# Suits_Board.net
KiCad netlist of a schematic drawn in EAGLE
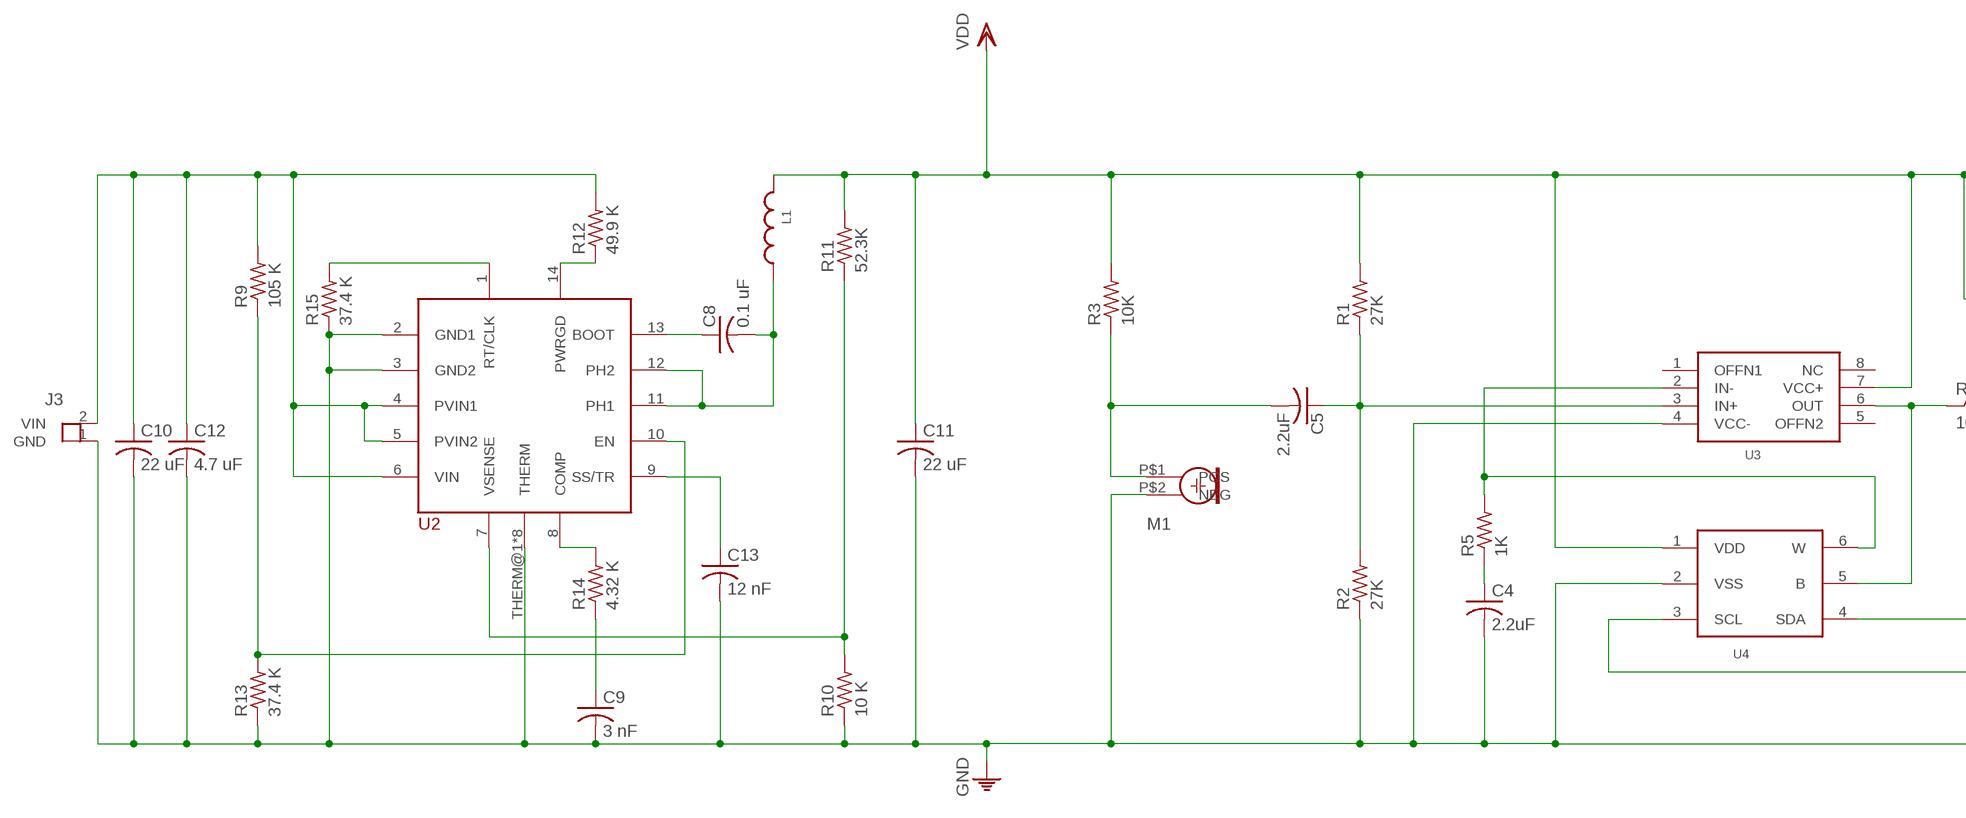
[diagram p0: schematic, sheet 1, part 1 of 2]
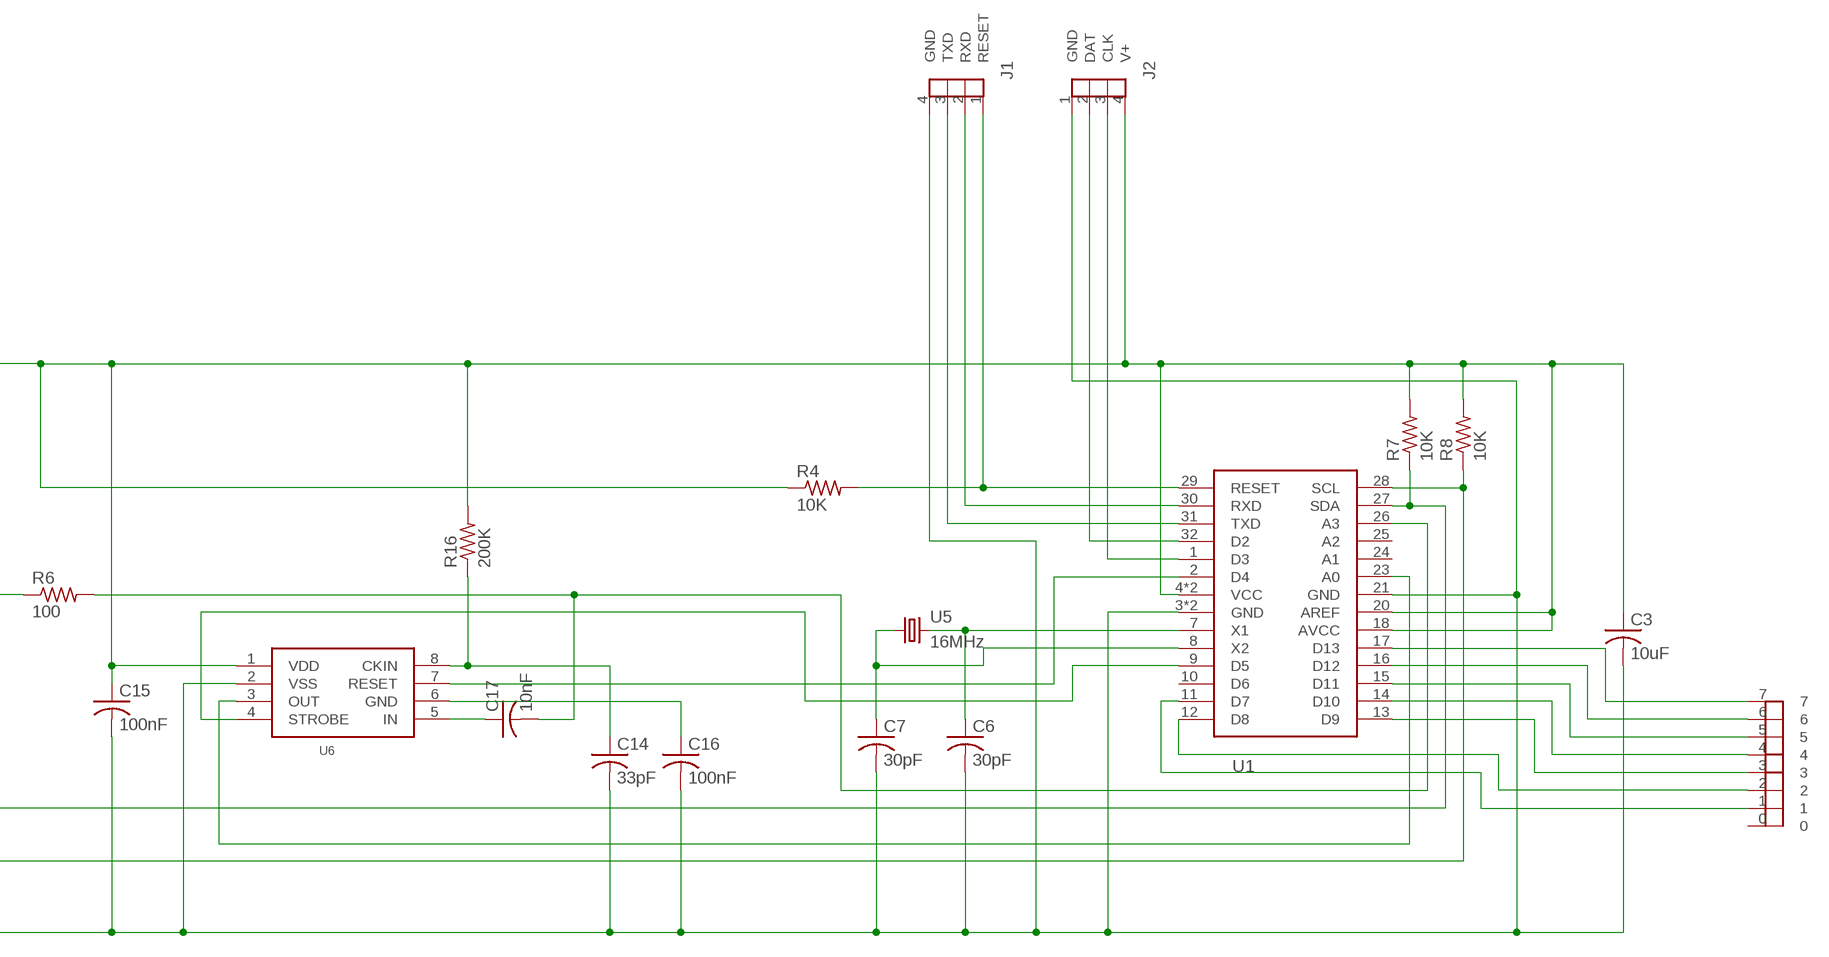
[diagram p1: schematic, sheet 1, part 2 of 2]

(export (version "E")
  (design (tool "Eeschema 10.0.6"))
  (components
    (comp (ref "C3")
      (value "10uF")
      (footprint "eagle-import:0805")
      (libsource (lib "eagle-import") (part "CAP0805"))
    )
    (comp (ref "C4")
      (value "2.2uF")
      (footprint "eagle-import:0603")
      (libsource (lib "eagle-import") (part "CAP0603"))
    )
    (comp (ref "C5")
      (value "2.2uF")
      (footprint "eagle-import:0603")
      (libsource (lib "eagle-import") (part "CAP0603"))
    )
    (comp (ref "C6")
      (value "30pF")
      (footprint "eagle-import:0603")
      (libsource (lib "eagle-import") (part "CAP0603"))
    )
    (comp (ref "C7")
      (value "30pF")
      (footprint "eagle-import:0603")
      (libsource (lib "eagle-import") (part "CAP0603"))
    )
    (comp (ref "C8")
      (value "0.1 uF")
      (footprint "eagle-import:0805")
      (libsource (lib "eagle-import") (part "CAP0805"))
    )
    (comp (ref "C9")
      (value "3 nF")
      (footprint "eagle-import:0805")
      (libsource (lib "eagle-import") (part "CAP0805"))
    )
    (comp (ref "C10")
      (value "22 uF")
      (footprint "eagle-import:1210")
      (libsource (lib "eagle-import") (part "CAP1210"))
    )
    (comp (ref "C11")
      (value "22 uF")
      (footprint "eagle-import:1210")
      (libsource (lib "eagle-import") (part "CAP1210"))
    )
    (comp (ref "C12")
      (value "4.7 uF")
      (footprint "eagle-import:0805")
      (libsource (lib "eagle-import") (part "CAP0805"))
    )
    (comp (ref "C13")
      (value "12 nF")
      (footprint "eagle-import:0402")
      (libsource (lib "eagle-import") (part "CAP0402"))
    )
    (comp (ref "C14")
      (value "33pF")
      (footprint "eagle-import:0402")
      (libsource (lib "eagle-import") (part "CAP0402"))
    )
    (comp (ref "C15")
      (value "100nF")
      (footprint "eagle-import:0805")
      (libsource (lib "eagle-import") (part "CAP0805"))
    )
    (comp (ref "C16")
      (value "100nF")
      (footprint "eagle-import:0805")
      (libsource (lib "eagle-import") (part "CAP0805"))
    )
    (comp (ref "C17")
      (value "10nF")
      (footprint "eagle-import:0402")
      (libsource (lib "eagle-import") (part "CAP0402"))
    )
    (comp (ref "J1")
      (value "PRGMCONN")
      (footprint "eagle-import:4CONN")
      (libsource (lib "eagle-import") (part "PRGMCONN"))
    )
    (comp (ref "J2")
      (value "LEDCONN")
      (footprint "eagle-import:4CONN")
      (libsource (lib "eagle-import") (part "LEDCONN"))
    )
    (comp (ref "J3")
      (value "PWRCONN")
      (footprint "eagle-import:2CONN")
      (libsource (lib "eagle-import") (part "PWRCONN"))
    )
    (comp (ref "L1")
      (value "VLF10045T")
      (footprint "eagle-import:VLF10045")
      (libsource (lib "eagle-import") (part "VLF10045T"))
    )
    (comp (ref "M1")
      (value "ELEC_MIC")
      (footprint "eagle-import:ELEC_MIC")
      (libsource (lib "eagle-import") (part "ELEC_MIC"))
    )
    (comp (ref "R1")
      (value "27K")
      (footprint "eagle-import:0603")
      (libsource (lib "eagle-import") (part "RESISTOR"))
    )
    (comp (ref "R2")
      (value "27K")
      (footprint "eagle-import:0603")
      (libsource (lib "eagle-import") (part "RESISTOR"))
    )
    (comp (ref "R3")
      (value "10K")
      (footprint "eagle-import:0603")
      (libsource (lib "eagle-import") (part "RESISTOR"))
    )
    (comp (ref "R4")
      (value "10K")
      (footprint "eagle-import:0603")
      (libsource (lib "eagle-import") (part "RESISTOR"))
    )
    (comp (ref "R5")
      (value "1K")
      (footprint "eagle-import:0603")
      (libsource (lib "eagle-import") (part "RESISTOR"))
    )
    (comp (ref "R6")
      (value "100")
      (footprint "eagle-import:0603")
      (libsource (lib "eagle-import") (part "RESISTOR"))
    )
    (comp (ref "R7")
      (value "10K")
      (footprint "eagle-import:0603")
      (libsource (lib "eagle-import") (part "RESISTOR"))
    )
    (comp (ref "R8")
      (value "10K")
      (footprint "eagle-import:0603")
      (libsource (lib "eagle-import") (part "RESISTOR"))
    )
    (comp (ref "R9")
      (value "105 K")
      (footprint "eagle-import:0402")
      (libsource (lib "eagle-import") (part "R0402"))
    )
    (comp (ref "R10")
      (value "10 K")
      (footprint "eagle-import:0402")
      (libsource (lib "eagle-import") (part "R0402"))
    )
    (comp (ref "R11")
      (value "52.3K")
      (footprint "eagle-import:0402")
      (libsource (lib "eagle-import") (part "R0402"))
    )
    (comp (ref "R12")
      (value "49.9 K")
      (footprint "eagle-import:0402")
      (libsource (lib "eagle-import") (part "R0402"))
    )
    (comp (ref "R13")
      (value "37.4 K")
      (footprint "eagle-import:0402")
      (libsource (lib "eagle-import") (part "R0402"))
    )
    (comp (ref "R14")
      (value "4.32 K")
      (footprint "eagle-import:0402")
      (libsource (lib "eagle-import") (part "R0402"))
    )
    (comp (ref "R15")
      (value "37.4 K")
      (footprint "eagle-import:0402")
      (libsource (lib "eagle-import") (part "R0402"))
    )
    (comp (ref "R16")
      (value "200K")
      (footprint "eagle-import:0603")
      (libsource (lib "eagle-import") (part "RESISTOR"))
    )
    (comp (ref "U$1")
      (value "KEYPAD")
      (footprint "eagle-import:KEYPAD")
      (libsource (lib "eagle-import") (part "KEYPAD"))
    )
    (comp (ref "U1")
      (value "ATMEGA328P")
      (footprint "eagle-import:TQFP32-08")
      (libsource (lib "eagle-import") (part "ATMEGA328P"))
    )
    (comp (ref "U2")
      (value "TPS54620")
      (footprint "eagle-import:14-VFQFN")
      (libsource (lib "eagle-import") (part "TPS54620"))
    )
    (comp (ref "U3")
      (value "TL071")
      (footprint "eagle-import:8-SOIC")
      (libsource (lib "eagle-import") (part "TL071"))
    )
    (comp (ref "U4")
      (value "MCP4017")
      (footprint "eagle-import:SOT-363")
      (libsource (lib "eagle-import") (part "MCP4017"))
    )
    (comp (ref "U5")
      (value "16MHz")
      (footprint "eagle-import:HC49_US")
      (libsource (lib "eagle-import") (part "CRYSTAL"))
    )
    (comp (ref "U6")
      (value "FFT IC")
      (footprint "eagle-import:DIP8")
      (libsource (lib "eagle-import") (part "MSGEQ7"))
    )
  )
  (nets
    (net (code "1") (name "GND") (class "Default")
      (node (ref "C10") (pin "P$2") (pinfunction "2_P$2") (pintype "passive"))
      (node (ref "C11") (pin "P$2") (pinfunction "2_P$2") (pintype "passive"))
      (node (ref "C12") (pin "A1") (pinfunction "2_A1") (pintype "passive"))
      (node (ref "C13") (pin "P$2") (pinfunction "2_P$2") (pintype "passive"))
      (node (ref "C14") (pin "P$2") (pinfunction "2_P$2") (pintype "passive"))
      (node (ref "C15") (pin "A1") (pinfunction "2_A1") (pintype "passive"))
      (node (ref "C16") (pin "A1") (pinfunction "2_A1") (pintype "passive"))
      (node (ref "C3") (pin "A1") (pinfunction "2_A1") (pintype "passive"))
      (node (ref "C4") (pin "2") (pinfunction "2_2") (pintype "passive"))
      (node (ref "C6") (pin "2") (pinfunction "2_2") (pintype "passive"))
      (node (ref "C7") (pin "2") (pinfunction "2_2") (pintype "passive"))
      (node (ref "C9") (pin "A1") (pinfunction "2_A1") (pintype "passive"))
      (node (ref "J1") (pin "4") (pinfunction "GND_4") (pintype "bidirectional"))
      (node (ref "J2") (pin "1") (pinfunction "GND_1") (pintype "bidirectional"))
      (node (ref "J3") (pin "1") (pinfunction "GND_1") (pintype "bidirectional"))
      (node (ref "M1") (pin "P$2") (pinfunction "NEG_P$2") (pintype "passive"))
      (node (ref "R10") (pin "P$1") (pinfunction "1_P$1") (pintype "passive"))
      (node (ref "R13") (pin "P$1") (pinfunction "1_P$1") (pintype "passive"))
      (node (ref "R15") (pin "P$1") (pinfunction "1_P$1") (pintype "passive"))
      (node (ref "R2") (pin "1") (pinfunction "1_1") (pintype "passive"))
      (node (ref "U1") (pin "21") (pinfunction "GND_21") (pintype "bidirectional"))
      (node (ref "U1") (pin "3") (pinfunction "GND_3") (pintype "bidirectional"))
      (node (ref "U1") (pin "5") (pinfunction "GND_5") (pintype "bidirectional"))
      (node (ref "U2") (pin "2") (pinfunction "GND1_2") (pintype "bidirectional"))
      (node (ref "U2") (pin "3") (pinfunction "GND2_3") (pintype "bidirectional"))
      (node (ref "U2") (pin "THERM@1") (pinfunction "THERM_THERM@1") (pintype "bidirectional"))
      (node (ref "U2") (pin "THERM@2") (pinfunction "THERM_THERM@2") (pintype "bidirectional"))
      (node (ref "U2") (pin "THERM@3") (pinfunction "THERM_THERM@3") (pintype "bidirectional"))
      (node (ref "U2") (pin "THERM@4") (pinfunction "THERM_THERM@4") (pintype "bidirectional"))
      (node (ref "U2") (pin "THERM@5") (pinfunction "THERM_THERM@5") (pintype "bidirectional"))
      (node (ref "U2") (pin "THERM@6") (pinfunction "THERM_THERM@6") (pintype "bidirectional"))
      (node (ref "U2") (pin "THERM@7") (pinfunction "THERM_THERM@7") (pintype "bidirectional"))
      (node (ref "U2") (pin "THERM@8") (pinfunction "THERM_THERM@8") (pintype "bidirectional"))
      (node (ref "U3") (pin "4") (pinfunction "VCC-_4") (pintype "bidirectional"))
      (node (ref "U4") (pin "2") (pinfunction "VSS_2") (pintype "bidirectional"))
      (node (ref "U6") (pin "2") (pinfunction "VSS_2") (pintype "bidirectional"))
    )
    (net (code "2") (name "Net-(C4-Pad1)") (class "Default")
      (node (ref "C4") (pin "1") (pinfunction "1_1") (pintype "passive"))
      (node (ref "R5") (pin "1") (pinfunction "1_1") (pintype "passive"))
    )
    (net (code "3") (name "Net-(C8-1)") (class "Default")
      (node (ref "C8") (pin "A") (pinfunction "1_A") (pintype "passive"))
      (node (ref "U2") (pin "13") (pinfunction "BOOT_13") (pintype "bidirectional"))
    )
    (net (code "4") (name "Net-(C8-2)") (class "Default")
      (node (ref "C8") (pin "A1") (pinfunction "2_A1") (pintype "passive"))
      (node (ref "L1") (pin "P$1") (pinfunction "1_P$1") (pintype "passive"))
      (node (ref "U2") (pin "11") (pinfunction "PH1_11") (pintype "bidirectional"))
      (node (ref "U2") (pin "12") (pinfunction "PH2_12") (pintype "bidirectional"))
    )
    (net (code "5") (name "Net-(C9-1)") (class "Default")
      (node (ref "C9") (pin "A") (pinfunction "1_A") (pintype "passive"))
      (node (ref "R14") (pin "P$1") (pinfunction "1_P$1") (pintype "passive"))
    )
    (net (code "6") (name "Net-(C10-1)") (class "Default")
      (node (ref "C10") (pin "P$1") (pinfunction "1_P$1") (pintype "passive"))
      (node (ref "C12") (pin "A") (pinfunction "1_A") (pintype "passive"))
      (node (ref "J3") (pin "2") (pinfunction "VIN_2") (pintype "bidirectional"))
      (node (ref "R12") (pin "P$2") (pinfunction "2_P$2") (pintype "passive"))
      (node (ref "R9") (pin "P$2") (pinfunction "2_P$2") (pintype "passive"))
      (node (ref "U2") (pin "4") (pinfunction "PVIN1_4") (pintype "bidirectional"))
      (node (ref "U2") (pin "5") (pinfunction "PVIN2_5") (pintype "bidirectional"))
      (node (ref "U2") (pin "6") (pinfunction "VIN_6") (pintype "bidirectional"))
    )
    (net (code "7") (name "Net-(C13-1)") (class "Default")
      (node (ref "C13") (pin "P$1") (pinfunction "1_P$1") (pintype "passive"))
      (node (ref "U2") (pin "9") (pinfunction "SS/TR_9") (pintype "bidirectional"))
    )
    (net (code "8") (name "Net-(C14-1)") (class "Default")
      (node (ref "C14") (pin "P$1") (pinfunction "1_P$1") (pintype "passive"))
      (node (ref "R16") (pin "1") (pinfunction "1_1") (pintype "passive"))
      (node (ref "U6") (pin "8") (pinfunction "CKIN_8") (pintype "bidirectional"))
    )
    (net (code "9") (name "Net-(C16-1)") (class "Default")
      (node (ref "C16") (pin "A") (pinfunction "1_A") (pintype "passive"))
      (node (ref "U6") (pin "6") (pinfunction "GND_6") (pintype "bidirectional"))
    )
    (net (code "10") (name "Net-(C17-1)") (class "Default")
      (node (ref "C17") (pin "P$1") (pinfunction "1_P$1") (pintype "passive"))
      (node (ref "U6") (pin "5") (pinfunction "IN_5") (pintype "bidirectional"))
    )
    (net (code "11") (name "Net-(C17-2)") (class "Default")
      (node (ref "C17") (pin "P$2") (pinfunction "2_P$2") (pintype "passive"))
      (node (ref "R6") (pin "2") (pinfunction "2_2") (pintype "passive"))
      (node (ref "U1") (pin "26") (pinfunction "A3_26") (pintype "bidirectional"))
    )
    (net (code "12") (name "Net-(J1-RESET)") (class "Default")
      (node (ref "J1") (pin "1") (pinfunction "RESET_1") (pintype "bidirectional"))
      (node (ref "R4") (pin "2") (pinfunction "2_2") (pintype "passive"))
      (node (ref "U1") (pin "29") (pinfunction "RESET_29") (pintype "bidirectional"))
    )
    (net (code "13") (name "Net-(J1-RXD)") (class "Default")
      (node (ref "J1") (pin "2") (pinfunction "RXD_2") (pintype "bidirectional"))
      (node (ref "U1") (pin "30") (pinfunction "RXD_30") (pintype "bidirectional"))
    )
    (net (code "14") (name "Net-(J1-TXD)") (class "Default")
      (node (ref "J1") (pin "3") (pinfunction "TXD_3") (pintype "bidirectional"))
      (node (ref "U1") (pin "31") (pinfunction "TXD_31") (pintype "bidirectional"))
    )
    (net (code "15") (name "Net-(J2-CLK)") (class "Default")
      (node (ref "J2") (pin "3") (pinfunction "CLK_3") (pintype "bidirectional"))
      (node (ref "U1") (pin "1") (pinfunction "D3_1") (pintype "bidirectional"))
    )
    (net (code "16") (name "Net-(J2-DAT)") (class "Default")
      (node (ref "J2") (pin "2") (pinfunction "DAT_2") (pintype "bidirectional"))
      (node (ref "U1") (pin "32") (pinfunction "D2_32") (pintype "bidirectional"))
    )
    (net (code "17") (name "Net-(M1-POS)") (class "Default")
      (node (ref "C5") (pin "2") (pinfunction "2_2") (pintype "passive"))
      (node (ref "M1") (pin "P$1") (pinfunction "POS_P$1") (pintype "passive"))
      (node (ref "R3") (pin "1") (pinfunction "1_1") (pintype "passive"))
    )
    (net (code "18") (name "Net-(R10-2)") (class "Default")
      (node (ref "R10") (pin "P$2") (pinfunction "2_P$2") (pintype "passive"))
      (node (ref "R11") (pin "P$1") (pinfunction "1_P$1") (pintype "passive"))
      (node (ref "U2") (pin "7") (pinfunction "VSENSE_7") (pintype "bidirectional"))
    )
    (net (code "19") (name "Net-(R12-1)") (class "Default")
      (node (ref "R12") (pin "P$1") (pinfunction "1_P$1") (pintype "passive"))
      (node (ref "U2") (pin "14") (pinfunction "PWRGD_14") (pintype "bidirectional"))
    )
    (net (code "20") (name "Net-(R13-2)") (class "Default")
      (node (ref "R13") (pin "P$2") (pinfunction "2_P$2") (pintype "passive"))
      (node (ref "R9") (pin "P$1") (pinfunction "1_P$1") (pintype "passive"))
      (node (ref "U2") (pin "10") (pinfunction "EN_10") (pintype "bidirectional"))
    )
    (net (code "21") (name "Net-(R14-2)") (class "Default")
      (node (ref "R14") (pin "P$2") (pinfunction "2_P$2") (pintype "passive"))
      (node (ref "U2") (pin "8") (pinfunction "COMP_8") (pintype "bidirectional"))
    )
    (net (code "22") (name "Net-(R15-2)") (class "Default")
      (node (ref "R15") (pin "P$2") (pinfunction "2_P$2") (pintype "passive"))
      (node (ref "U2") (pin "1") (pinfunction "RT/CLK_1") (pintype "bidirectional"))
    )
    (net (code "23") (name "Net-(U1-A0)") (class "Default")
      (node (ref "U1") (pin "23") (pinfunction "A0_23") (pintype "bidirectional"))
      (node (ref "U6") (pin "3") (pinfunction "OUT_3") (pintype "bidirectional"))
    )
    (net (code "24") (name "Net-(U1-D4)") (class "Default")
      (node (ref "U1") (pin "2") (pinfunction "D4_2") (pintype "bidirectional"))
      (node (ref "U6") (pin "7") (pinfunction "RESET_7") (pintype "bidirectional"))
    )
    (net (code "25") (name "Net-(U1-D5)") (class "Default")
      (node (ref "U1") (pin "9") (pinfunction "D5_9") (pintype "bidirectional"))
      (node (ref "U6") (pin "4") (pinfunction "STROBE_4") (pintype "bidirectional"))
    )
    (net (code "26") (name "Net-(U1-D7)") (class "Default")
      (node (ref "U$1") (pin "1") (pinfunction "1_1") (pintype "bidirectional"))
      (node (ref "U1") (pin "11") (pinfunction "D7_11") (pintype "bidirectional"))
    )
    (net (code "27") (name "Net-(U1-D8)") (class "Default")
      (node (ref "U$1") (pin "2") (pinfunction "2_2") (pintype "bidirectional"))
      (node (ref "U1") (pin "12") (pinfunction "D8_12") (pintype "bidirectional"))
    )
    (net (code "28") (name "Net-(U1-D9)") (class "Default")
      (node (ref "U$1") (pin "3") (pinfunction "3_3") (pintype "bidirectional"))
      (node (ref "U1") (pin "13") (pinfunction "D9_13") (pintype "bidirectional"))
    )
    (net (code "29") (name "Net-(U1-D10)") (class "Default")
      (node (ref "U$1") (pin "4") (pinfunction "4_4") (pintype "bidirectional"))
      (node (ref "U1") (pin "14") (pinfunction "D10_14") (pintype "bidirectional"))
    )
    (net (code "30") (name "Net-(U1-D11)") (class "Default")
      (node (ref "U$1") (pin "5") (pinfunction "5_5") (pintype "bidirectional"))
      (node (ref "U1") (pin "15") (pinfunction "D11_15") (pintype "bidirectional"))
    )
    (net (code "31") (name "Net-(U1-D12)") (class "Default")
      (node (ref "U$1") (pin "6") (pinfunction "6_6") (pintype "bidirectional"))
      (node (ref "U1") (pin "16") (pinfunction "D12_16") (pintype "bidirectional"))
    )
    (net (code "32") (name "Net-(U1-D13)") (class "Default")
      (node (ref "U$1") (pin "7") (pinfunction "7_7") (pintype "bidirectional"))
      (node (ref "U1") (pin "17") (pinfunction "D13_17") (pintype "bidirectional"))
    )
    (net (code "33") (name "Net-(U1-SCL)") (class "Default")
      (node (ref "R8") (pin "1") (pinfunction "1_1") (pintype "passive"))
      (node (ref "U1") (pin "28") (pinfunction "SCL_28") (pintype "bidirectional"))
      (node (ref "U4") (pin "3") (pinfunction "SCL_3") (pintype "bidirectional"))
    )
    (net (code "34") (name "Net-(U1-SDA)") (class "Default")
      (node (ref "R7") (pin "1") (pinfunction "1_1") (pintype "passive"))
      (node (ref "U1") (pin "27") (pinfunction "SDA_27") (pintype "bidirectional"))
      (node (ref "U4") (pin "4") (pinfunction "SDA_4") (pintype "bidirectional"))
    )
    (net (code "35") (name "Net-(U1-X1)") (class "Default")
      (node (ref "C6") (pin "1") (pinfunction "1_1") (pintype "passive"))
      (node (ref "U1") (pin "7") (pinfunction "X1_7") (pintype "bidirectional"))
      (node (ref "U5") (pin "P$2") (pinfunction "2_P$2") (pintype "passive"))
    )
    (net (code "36") (name "Net-(U1-X2)") (class "Default")
      (node (ref "C7") (pin "1") (pinfunction "1_1") (pintype "passive"))
      (node (ref "U1") (pin "8") (pinfunction "X2_8") (pintype "bidirectional"))
      (node (ref "U5") (pin "P$1") (pinfunction "1_P$1") (pintype "passive"))
    )
    (net (code "37") (name "Net-(U3-IN+)") (class "Default")
      (node (ref "C5") (pin "1") (pinfunction "1_1") (pintype "passive"))
      (node (ref "R1") (pin "1") (pinfunction "1_1") (pintype "passive"))
      (node (ref "R2") (pin "2") (pinfunction "2_2") (pintype "passive"))
      (node (ref "U3") (pin "3") (pinfunction "IN+_3") (pintype "bidirectional"))
    )
    (net (code "38") (name "Net-(U3-IN-)") (class "Default")
      (node (ref "R5") (pin "2") (pinfunction "2_2") (pintype "passive"))
      (node (ref "U3") (pin "2") (pinfunction "IN-_2") (pintype "bidirectional"))
      (node (ref "U4") (pin "6") (pinfunction "W_6") (pintype "bidirectional"))
    )
    (net (code "39") (name "Net-(U3-OUT)") (class "Default")
      (node (ref "R6") (pin "1") (pinfunction "1_1") (pintype "passive"))
      (node (ref "U3") (pin "6") (pinfunction "OUT_6") (pintype "bidirectional"))
      (node (ref "U4") (pin "5") (pinfunction "B_5") (pintype "bidirectional"))
    )
    (net (code "40") (name "VDD") (class "Default")
      (node (ref "C11") (pin "P$1") (pinfunction "1_P$1") (pintype "passive"))
      (node (ref "C15") (pin "A") (pinfunction "1_A") (pintype "passive"))
      (node (ref "C3") (pin "A") (pinfunction "1_A") (pintype "passive"))
      (node (ref "J2") (pin "4") (pinfunction "V+_4") (pintype "bidirectional"))
      (node (ref "L1") (pin "P$2") (pinfunction "2_P$2") (pintype "passive"))
      (node (ref "R1") (pin "2") (pinfunction "2_2") (pintype "passive"))
      (node (ref "R11") (pin "P$2") (pinfunction "2_P$2") (pintype "passive"))
      (node (ref "R16") (pin "2") (pinfunction "2_2") (pintype "passive"))
      (node (ref "R3") (pin "2") (pinfunction "2_2") (pintype "passive"))
      (node (ref "R4") (pin "1") (pinfunction "1_1") (pintype "passive"))
      (node (ref "R7") (pin "2") (pinfunction "2_2") (pintype "passive"))
      (node (ref "R8") (pin "2") (pinfunction "2_2") (pintype "passive"))
      (node (ref "U1") (pin "18") (pinfunction "AVCC_18") (pintype "bidirectional"))
      (node (ref "U1") (pin "20") (pinfunction "AREF_20") (pintype "bidirectional"))
      (node (ref "U1") (pin "4") (pinfunction "VCC_4") (pintype "bidirectional"))
      (node (ref "U1") (pin "6") (pinfunction "VCC_6") (pintype "bidirectional"))
      (node (ref "U3") (pin "7") (pinfunction "VCC+_7") (pintype "bidirectional"))
      (node (ref "U4") (pin "1") (pinfunction "VDD_1") (pintype "bidirectional"))
      (node (ref "U6") (pin "1") (pinfunction "VDD_1") (pintype "bidirectional"))
    )
    (net (code "41") (name "unconnected-(U$1-Pad0)") (class "Default")
      (node (ref "U$1") (pin "0") (pinfunction "0_0") (pintype "bidirectional"))
    )
    (net (code "42") (name "unconnected-(U1-A1-Pad24)") (class "Default")
      (node (ref "U1") (pin "24") (pinfunction "A1_24") (pintype "bidirectional"))
    )
    (net (code "43") (name "unconnected-(U1-A2-Pad25)") (class "Default")
      (node (ref "U1") (pin "25") (pinfunction "A2_25") (pintype "bidirectional"))
    )
    (net (code "44") (name "unconnected-(U1-D6-Pad10)") (class "Default")
      (node (ref "U1") (pin "10") (pinfunction "D6_10") (pintype "bidirectional"))
    )
    (net (code "45") (name "unconnected-(U3-NC-Pad8)") (class "Default")
      (node (ref "U3") (pin "8") (pinfunction "NC_8") (pintype "bidirectional"))
    )
    (net (code "46") (name "unconnected-(U3-OFFN1-Pad1)") (class "Default")
      (node (ref "U3") (pin "1") (pinfunction "OFFN1_1") (pintype "bidirectional"))
    )
    (net (code "47") (name "unconnected-(U3-OFFN2-Pad5)") (class "Default")
      (node (ref "U3") (pin "5") (pinfunction "OFFN2_5") (pintype "bidirectional"))
    )
  )
)
